# uvi-2_1.net
KiCad netlist of a schematic drawn in EAGLE
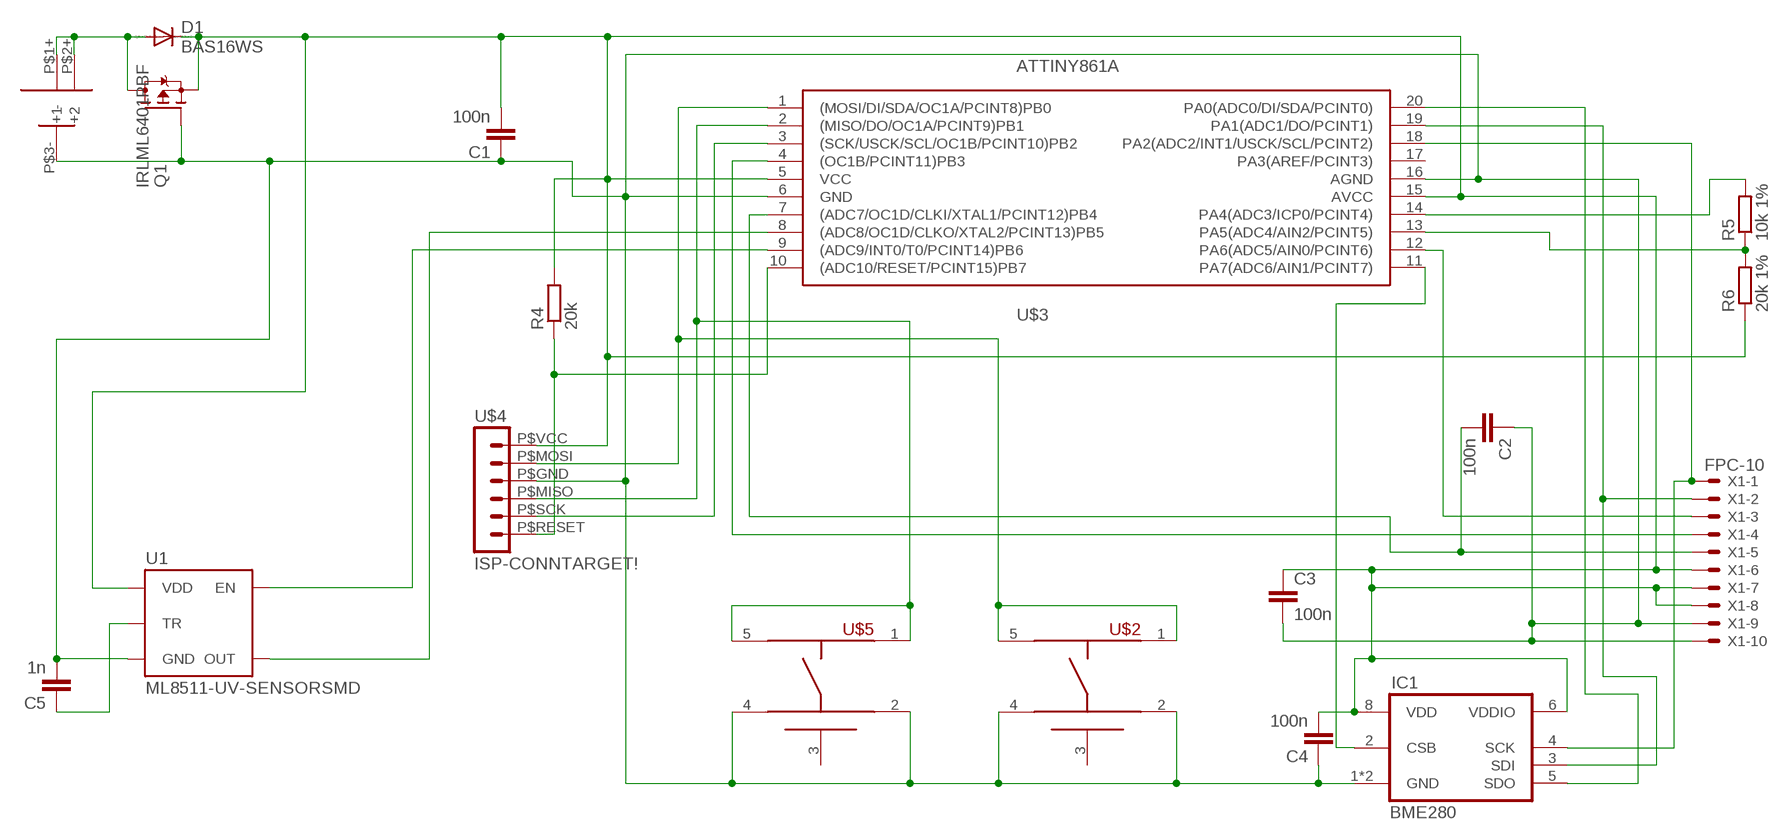
[diagram p0: schematic, sheet 1]

(export (version "E")
  (design (tool "Eeschema 10.0.6"))
  (components
    (comp (ref "C1")
      (value "100n")
      (footprint "eagle-import:C0805")
      (libsource (lib "eagle-import") (part "C-EUC0805"))
    )
    (comp (ref "C2")
      (value "100n")
      (footprint "eagle-import:C0805")
      (libsource (lib "eagle-import") (part "C-EUC0805"))
    )
    (comp (ref "C3")
      (value "100n")
      (footprint "eagle-import:C0805")
      (libsource (lib "eagle-import") (part "C-EUC0805"))
    )
    (comp (ref "C4")
      (value "100n")
      (footprint "eagle-import:C0805")
      (libsource (lib "eagle-import") (part "C-EUC0805"))
    )
    (comp (ref "C5")
      (value "1n")
      (footprint "eagle-import:C0805")
      (libsource (lib "eagle-import") (part "C-EUC0805"))
    )
    (comp (ref "D1")
      (value "BAS16WS")
      (footprint "eagle-import:SOD323-W")
      (libsource (lib "eagle-import") (part "BAS16WS"))
    )
    (comp (ref "IC1")
      (value "BME280")
      (footprint "eagle-import:BMP280")
      (libsource (lib "eagle-import") (part "BME280"))
    )
    (comp (ref "Q1")
      (value "IRLML6401PBF")
      (footprint "eagle-import:SOT23")
      (libsource (lib "eagle-import") (part "IRLML6401PBF"))
    )
    (comp (ref "R4")
      (value "20k")
      (footprint "eagle-import:R0805")
      (libsource (lib "eagle-import") (part "R-EU_R0805"))
    )
    (comp (ref "R5")
      (value "10k 1%")
      (footprint "eagle-import:R0805")
      (libsource (lib "eagle-import") (part "R-EU_R0805"))
    )
    (comp (ref "R6")
      (value "20k 1%")
      (footprint "eagle-import:R0805")
      (libsource (lib "eagle-import") (part "R-EU_R0805"))
    )
    (comp (ref "U$1")
      (value "CR2016")
      (footprint "eagle-import:BAT-HLD-002")
      (libsource (lib "eagle-import") (part "CR2016"))
    )
    (comp (ref "U$2")
      (value "KMSXXXG")
      (footprint "eagle-import:C&K-KMS-SWITCH")
      (libsource (lib "eagle-import") (part "KMSXXXG"))
    )
    (comp (ref "U$3")
      (value "ATTINY861A")
      (footprint "eagle-import:TSSOP20")
      (libsource (lib "eagle-import") (part "ATTINY861A"))
    )
    (comp (ref "U$4")
      (value "ISP-CONNTARGET!")
      (footprint "eagle-import:ISP-TARGET")
      (libsource (lib "eagle-import") (part "ISP-CONNTARGET!"))
    )
    (comp (ref "U$5")
      (value "KMSXXXG")
      (footprint "eagle-import:C&K-KMS-SWITCH")
      (libsource (lib "eagle-import") (part "KMSXXXG"))
    )
    (comp (ref "U1")
      (value "ML8511-UV-SENSORSMD")
      (footprint "eagle-import:ML8511")
      (libsource (lib "eagle-import") (part "ML8511-UV-SENSORSMD"))
    )
    (comp (ref "X1")
      (value "FPC-10")
      (footprint "eagle-import:FPC-10-BTM")
      (libsource (lib "eagle-import") (part "FPC-10"))
    )
  )
  (nets
    (net (code "1") (name "Net-(IC1-CSB)") (class "Default")
      (node (ref "IC1") (pin "2") (pinfunction "CSB_2") (pintype "input"))
      (node (ref "U$3") (pin "11") (pinfunction "PA7(ADC6/AIN1/PCINT7)_11") (pintype "bidirectional"))
    )
    (net (code "2") (name "Net-(IC1-SCK)") (class "Default")
      (node (ref "IC1") (pin "4") (pinfunction "SCK_4") (pintype "bidirectional"))
      (node (ref "U$3") (pin "18") (pinfunction "PA2(ADC2/INT1/USCK/SCL/PCINT2)_18") (pintype "bidirectional"))
      (node (ref "X1") (pin "P$1") (pinfunction "S_P$1") (pintype "passive"))
    )
    (net (code "3") (name "Net-(IC1-SDI)") (class "Default")
      (node (ref "IC1") (pin "3") (pinfunction "SDI_3") (pintype "bidirectional"))
      (node (ref "U$3") (pin "19") (pinfunction "PA1(ADC1/DO/PCINT1)_19") (pintype "bidirectional"))
      (node (ref "X1") (pin "P$2") (pinfunction "S_P$2") (pintype "passive"))
    )
    (net (code "4") (name "Net-(IC1-SDO)") (class "Default")
      (node (ref "IC1") (pin "5") (pinfunction "SDO_5") (pintype "input"))
      (node (ref "U$3") (pin "20") (pinfunction "PA0(ADC0/DI/SDA/PCINT0)_20") (pintype "bidirectional"))
    )
    (net (code "5") (name "Net-(IC1-VDD)") (class "Default")
      (node (ref "C1") (pin "2") (pinfunction "2_2") (pintype "passive"))
      (node (ref "C3") (pin "1") (pinfunction "1_1") (pintype "passive"))
      (node (ref "C4") (pin "2") (pinfunction "2_2") (pintype "passive"))
      (node (ref "D1") (pin "C") (pinfunction "C_C") (pintype "passive"))
      (node (ref "IC1") (pin "6") (pinfunction "VDDIO_6") (pintype "power_in"))
      (node (ref "IC1") (pin "8") (pinfunction "VDD_8") (pintype "power_in"))
      (node (ref "Q1") (pin "2") (pinfunction "S_2") (pintype "passive"))
      (node (ref "R4") (pin "2") (pinfunction "2_2") (pintype "passive"))
      (node (ref "R6") (pin "1") (pinfunction "1_1") (pintype "passive"))
      (node (ref "U$3") (pin "15") (pinfunction "AVCC_15") (pintype "power_in"))
      (node (ref "U$3") (pin "5") (pinfunction "VCC_5") (pintype "power_in"))
      (node (ref "U$4") (pin "P$VCC") (pinfunction "VCC_P$VCC") (pintype "passive"))
      (node (ref "U1") (pin "7") (pinfunction "VDD_7") (pintype "power_in"))
      (node (ref "X1") (pin "P$6") (pinfunction "S_P$6") (pintype "passive"))
      (node (ref "X1") (pin "P$7") (pinfunction "S_P$7") (pintype "passive"))
      (node (ref "X1") (pin "P$8") (pinfunction "S_P$8") (pintype "passive"))
    )
    (net (code "6") (name "Net-(Q1-D)") (class "Default")
      (node (ref "D1") (pin "A") (pinfunction "A_A") (pintype "passive"))
      (node (ref "Q1") (pin "3") (pinfunction "D_3") (pintype "passive"))
      (node (ref "U$1") (pin "P$1+") (pinfunction "+1_P$1+") (pintype "power_in"))
      (node (ref "U$1") (pin "P$2+") (pinfunction "+2_P$2+") (pintype "power_in"))
    )
    (net (code "7") (name "Net-(Q1-G)") (class "Default")
      (node (ref "C1") (pin "1") (pinfunction "1_1") (pintype "passive"))
      (node (ref "C2") (pin "1") (pinfunction "1_1") (pintype "passive"))
      (node (ref "C3") (pin "2") (pinfunction "2_2") (pintype "passive"))
      (node (ref "C4") (pin "1") (pinfunction "1_1") (pintype "passive"))
      (node (ref "C5") (pin "2") (pinfunction "2_2") (pintype "passive"))
      (node (ref "IC1") (pin "1") (pinfunction "GND_1") (pintype "power_in"))
      (node (ref "IC1") (pin "7") (pinfunction "GND_7") (pintype "power_in"))
      (node (ref "Q1") (pin "1") (pinfunction "G_1") (pintype "passive"))
      (node (ref "U$1") (pin "P$3-") (pinfunction "-_P$3-") (pintype "power_in"))
      (node (ref "U$2") (pin "2") (pinfunction "2_2") (pintype "bidirectional"))
      (node (ref "U$2") (pin "4") (pinfunction "4_4") (pintype "bidirectional"))
      (node (ref "U$3") (pin "16") (pinfunction "AGND_16") (pintype "power_in"))
      (node (ref "U$3") (pin "6") (pinfunction "GND_6") (pintype "power_in"))
      (node (ref "U$4") (pin "P$GND") (pinfunction "GND_P$GND") (pintype "passive"))
      (node (ref "U$5") (pin "2") (pinfunction "2_2") (pintype "bidirectional"))
      (node (ref "U$5") (pin "4") (pinfunction "4_4") (pintype "bidirectional"))
      (node (ref "U1") (pin "5") (pinfunction "GND_5") (pintype "power_in"))
      (node (ref "X1") (pin "P$10") (pinfunction "S_P$10") (pintype "passive"))
      (node (ref "X1") (pin "P$9") (pinfunction "S_P$9") (pintype "passive"))
    )
    (net (code "8") (name "Net-(U$3-(ADC7{slash}OC1D{slash}CLKI{slash}XTAL1{slash}PCINT12)PB4)") (class "Default")
      (node (ref "C2") (pin "2") (pinfunction "2_2") (pintype "passive"))
      (node (ref "U$3") (pin "7") (pinfunction "(ADC7/OC1D/CLKI/XTAL1/PCINT12)PB4_7") (pintype "bidirectional"))
      (node (ref "X1") (pin "P$5") (pinfunction "S_P$5") (pintype "passive"))
    )
    (net (code "9") (name "Net-(U$3-(ADC8{slash}OC1D{slash}CLKO{slash}XTAL2{slash}PCINT13)PB5)") (class "Default")
      (node (ref "U$3") (pin "8") (pinfunction "(ADC8/OC1D/CLKO/XTAL2/PCINT13)PB5_8") (pintype "bidirectional"))
      (node (ref "U1") (pin "8") (pinfunction "OUT_8") (pintype "output"))
    )
    (net (code "10") (name "Net-(U$3-(ADC9{slash}INT0{slash}T0{slash}PCINT14)PB6)") (class "Default")
      (node (ref "U$3") (pin "9") (pinfunction "(ADC9/INT0/T0/PCINT14)PB6_9") (pintype "bidirectional"))
      (node (ref "U1") (pin "4") (pinfunction "EN_4") (pintype "input"))
    )
    (net (code "11") (name "Net-(U$3-(ADC10{slash}RESET{slash}PCINT15)PB7)") (class "Default")
      (node (ref "R4") (pin "1") (pinfunction "1_1") (pintype "passive"))
      (node (ref "U$3") (pin "10") (pinfunction "(ADC10/RESET/PCINT15)PB7_10") (pintype "bidirectional"))
      (node (ref "U$4") (pin "P$RESET") (pinfunction "RESET_P$RESET") (pintype "passive"))
    )
    (net (code "12") (name "Net-(U$3-(MISO{slash}DO{slash}OC1A{slash}PCINT9)PB1)") (class "Default")
      (node (ref "U$3") (pin "2") (pinfunction "(MISO/DO/OC1A/PCINT9)PB1_2") (pintype "bidirectional"))
      (node (ref "U$4") (pin "P$MISO") (pinfunction "MISO_P$MISO") (pintype "passive"))
      (node (ref "U$5") (pin "1") (pinfunction "1_1") (pintype "bidirectional"))
      (node (ref "U$5") (pin "5") (pinfunction "5_5") (pintype "bidirectional"))
    )
    (net (code "13") (name "Net-(U$3-(MOSI{slash}DI{slash}SDA{slash}OC1A{slash}PCINT8)PB0)") (class "Default")
      (node (ref "U$2") (pin "1") (pinfunction "1_1") (pintype "bidirectional"))
      (node (ref "U$2") (pin "5") (pinfunction "5_5") (pintype "bidirectional"))
      (node (ref "U$3") (pin "1") (pinfunction "(MOSI/DI/SDA/OC1A/PCINT8)PB0_1") (pintype "bidirectional"))
      (node (ref "U$4") (pin "P$MOSI") (pinfunction "MOSI_P$MOSI") (pintype "passive"))
    )
    (net (code "14") (name "Net-(U$3-(OC1B{slash}PCINT11)PB3)") (class "Default")
      (node (ref "U$3") (pin "4") (pinfunction "(OC1B/PCINT11)PB3_4") (pintype "bidirectional"))
      (node (ref "X1") (pin "P$4") (pinfunction "S_P$4") (pintype "passive"))
    )
    (net (code "15") (name "Net-(U$3-(SCK{slash}USCK{slash}SCL{slash}OC1B{slash}PCINT10)PB2)") (class "Default")
      (node (ref "U$3") (pin "3") (pinfunction "(SCK/USCK/SCL/OC1B/PCINT10)PB2_3") (pintype "bidirectional"))
      (node (ref "U$4") (pin "P$SCK") (pinfunction "SCK_P$SCK") (pintype "passive"))
    )
    (net (code "16") (name "Net-(U$3-PA4(ADC3{slash}ICP0{slash}PCINT4))") (class "Default")
      (node (ref "R5") (pin "2") (pinfunction "2_2") (pintype "passive"))
      (node (ref "U$3") (pin "14") (pinfunction "PA4(ADC3/ICP0/PCINT4)_14") (pintype "bidirectional"))
    )
    (net (code "17") (name "Net-(U$3-PA5(ADC4{slash}AIN2{slash}PCINT5))") (class "Default")
      (node (ref "R5") (pin "1") (pinfunction "1_1") (pintype "passive"))
      (node (ref "R6") (pin "2") (pinfunction "2_2") (pintype "passive"))
      (node (ref "U$3") (pin "13") (pinfunction "PA5(ADC4/AIN2/PCINT5)_13") (pintype "bidirectional"))
    )
    (net (code "18") (name "Net-(U$3-PA6(ADC5{slash}AIN0{slash}PCINT6))") (class "Default")
      (node (ref "U$3") (pin "12") (pinfunction "PA6(ADC5/AIN0/PCINT6)_12") (pintype "bidirectional"))
      (node (ref "X1") (pin "P$3") (pinfunction "S_P$3") (pintype "passive"))
    )
    (net (code "19") (name "Net-(U1-TR)") (class "Default")
      (node (ref "C5") (pin "1") (pinfunction "1_1") (pintype "passive"))
      (node (ref "U1") (pin "10") (pinfunction "TR_10") (pintype "power_in"))
    )
    (net (code "20") (name "unconnected-(U$2-Pad3)") (class "Default")
      (node (ref "U$2") (pin "3") (pinfunction "3_3") (pintype "bidirectional"))
    )
    (net (code "21") (name "unconnected-(U$3-PA3(AREF{slash}PCINT3)-Pad17)") (class "Default")
      (node (ref "U$3") (pin "17") (pinfunction "PA3(AREF/PCINT3)_17") (pintype "bidirectional"))
    )
    (net (code "22") (name "unconnected-(U$5-Pad3)") (class "Default")
      (node (ref "U$5") (pin "3") (pinfunction "3_3") (pintype "bidirectional"))
    )
  )
)
